# flowShield.net
KiCad netlist of a schematic drawn in EAGLE
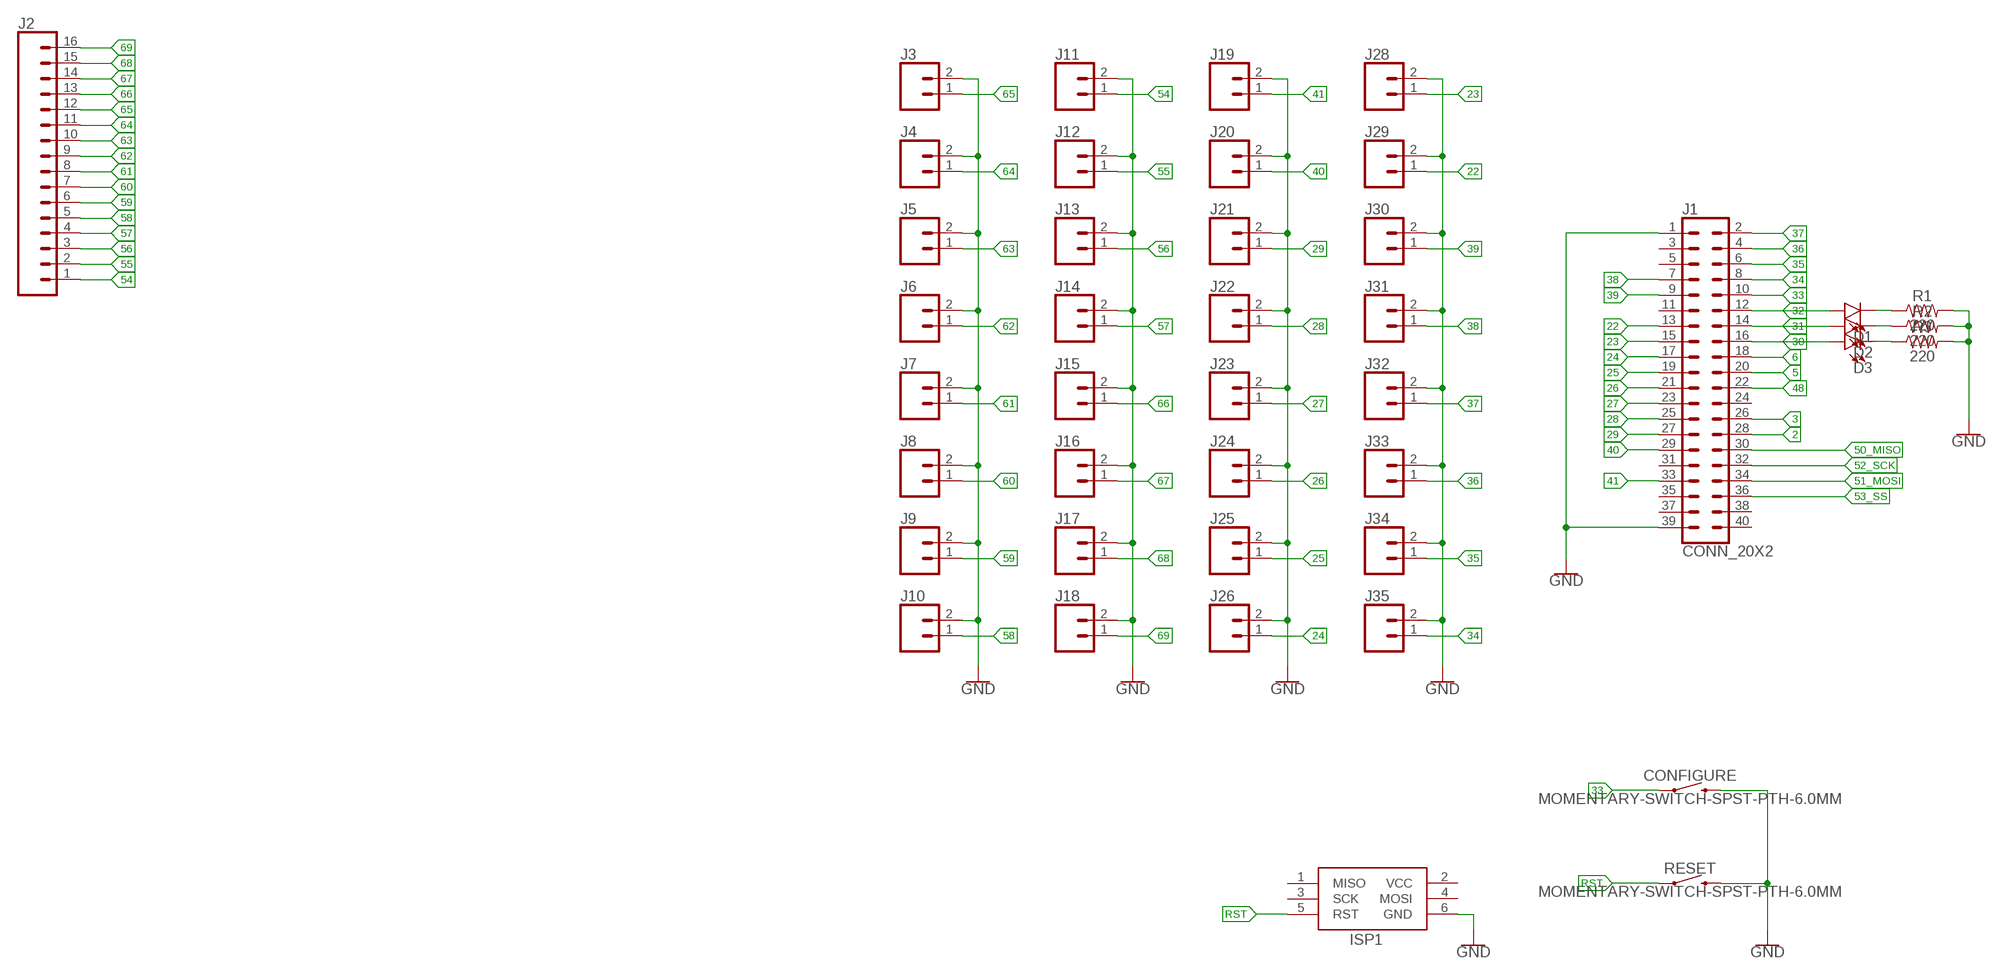
[diagram p0: schematic, sheet 1]

(export (version "E")
  (design (tool "Eeschema 10.0.6"))
  (components
    (comp (ref "CONFIGURE")
      (value "MOMENTARY-SWITCH-SPST-PTH-6.0MM")
      (footprint "eagle-import:TACTILE_SWITCH_PTH_6.0MM")
      (libsource (lib "eagle-import") (part "MOMENTARY-SWITCH-SPST-PTH-6.0MM"))
    )
    (comp (ref "D1")
      (value "LED3MM")
      (footprint "eagle-import:LED_3MM")
      (libsource (lib "eagle-import") (part "LED3MM"))
    )
    (comp (ref "D2")
      (value "LED3MM")
      (footprint "eagle-import:LED_3MM")
      (libsource (lib "eagle-import") (part "LED3MM"))
    )
    (comp (ref "D3")
      (value "LED3MM")
      (footprint "eagle-import:LED_3MM")
      (libsource (lib "eagle-import") (part "LED3MM"))
    )
    (comp (ref "ISP1")
      (value "ADAFRUIT_AVRISP-6")
      (footprint "eagle-import:ADAFRUIT_AVRISP")
      (libsource (lib "eagle-import") (part "ADAFRUIT_AVRISP-6"))
    )
    (comp (ref "J1")
      (value "CONN_20X2")
      (footprint "eagle-import:2X20")
      (libsource (lib "eagle-import") (part "CONN_20X2"))
    )
    (comp (ref "J2")
      (value "CONN_16")
      (footprint "eagle-import:1X16")
      (libsource (lib "eagle-import") (part "CONN_16"))
    )
    (comp (ref "J3")
      (value "CONN_025MM")
      (footprint "eagle-import:SCREWTERMINAL-5MM-2")
      (libsource (lib "eagle-import") (part "CONN_025MM"))
    )
    (comp (ref "J4")
      (value "CONN_025MM")
      (footprint "eagle-import:SCREWTERMINAL-5MM-2")
      (fields (field (name "SF_SKU") "PRT-08432"))
      (libsource (lib "eagle-import") (part "CONN_025MM"))
    )
    (comp (ref "J5")
      (value "CONN_025MM")
      (footprint "eagle-import:SCREWTERMINAL-5MM-2")
      (fields (field (name "SF_SKU") "PRT-08432"))
      (libsource (lib "eagle-import") (part "CONN_025MM"))
    )
    (comp (ref "J6")
      (value "CONN_025MM")
      (footprint "eagle-import:SCREWTERMINAL-5MM-2")
      (fields (field (name "SF_SKU") "PRT-08432"))
      (libsource (lib "eagle-import") (part "CONN_025MM"))
    )
    (comp (ref "J7")
      (value "CONN_025MM")
      (footprint "eagle-import:SCREWTERMINAL-5MM-2")
      (fields (field (name "SF_SKU") "PRT-08432"))
      (libsource (lib "eagle-import") (part "CONN_025MM"))
    )
    (comp (ref "J8")
      (value "CONN_025MM")
      (footprint "eagle-import:SCREWTERMINAL-5MM-2")
      (fields (field (name "SF_SKU") "PRT-08432"))
      (libsource (lib "eagle-import") (part "CONN_025MM"))
    )
    (comp (ref "J9")
      (value "CONN_025MM")
      (footprint "eagle-import:SCREWTERMINAL-5MM-2")
      (fields (field (name "SF_SKU") "PRT-08432"))
      (libsource (lib "eagle-import") (part "CONN_025MM"))
    )
    (comp (ref "J10")
      (value "CONN_025MM")
      (footprint "eagle-import:SCREWTERMINAL-5MM-2")
      (fields (field (name "SF_SKU") "PRT-08432"))
      (libsource (lib "eagle-import") (part "CONN_025MM"))
    )
    (comp (ref "J11")
      (value "CONN_025MM")
      (footprint "eagle-import:SCREWTERMINAL-5MM-2")
      (libsource (lib "eagle-import") (part "CONN_025MM"))
    )
    (comp (ref "J12")
      (value "CONN_025MM")
      (footprint "eagle-import:SCREWTERMINAL-5MM-2")
      (fields (field (name "SF_SKU") "PRT-08432"))
      (libsource (lib "eagle-import") (part "CONN_025MM"))
    )
    (comp (ref "J13")
      (value "CONN_025MM")
      (footprint "eagle-import:SCREWTERMINAL-5MM-2")
      (fields (field (name "SF_SKU") "PRT-08432"))
      (libsource (lib "eagle-import") (part "CONN_025MM"))
    )
    (comp (ref "J14")
      (value "CONN_025MM")
      (footprint "eagle-import:SCREWTERMINAL-5MM-2")
      (fields (field (name "SF_SKU") "PRT-08432"))
      (libsource (lib "eagle-import") (part "CONN_025MM"))
    )
    (comp (ref "J15")
      (value "CONN_025MM")
      (footprint "eagle-import:SCREWTERMINAL-5MM-2")
      (fields (field (name "SF_SKU") "PRT-08432"))
      (libsource (lib "eagle-import") (part "CONN_025MM"))
    )
    (comp (ref "J16")
      (value "CONN_025MM")
      (footprint "eagle-import:SCREWTERMINAL-5MM-2")
      (fields (field (name "SF_SKU") "PRT-08432"))
      (libsource (lib "eagle-import") (part "CONN_025MM"))
    )
    (comp (ref "J17")
      (value "CONN_025MM")
      (footprint "eagle-import:SCREWTERMINAL-5MM-2")
      (fields (field (name "SF_SKU") "PRT-08432"))
      (libsource (lib "eagle-import") (part "CONN_025MM"))
    )
    (comp (ref "J18")
      (value "CONN_025MM")
      (footprint "eagle-import:SCREWTERMINAL-5MM-2")
      (fields (field (name "SF_SKU") "PRT-08432"))
      (libsource (lib "eagle-import") (part "CONN_025MM"))
    )
    (comp (ref "J19")
      (value "CONN_025MM")
      (footprint "eagle-import:SCREWTERMINAL-5MM-2")
      (libsource (lib "eagle-import") (part "CONN_025MM"))
    )
    (comp (ref "J20")
      (value "CONN_025MM")
      (footprint "eagle-import:SCREWTERMINAL-5MM-2")
      (fields (field (name "SF_SKU") "PRT-08432"))
      (libsource (lib "eagle-import") (part "CONN_025MM"))
    )
    (comp (ref "J21")
      (value "CONN_025MM")
      (footprint "eagle-import:SCREWTERMINAL-5MM-2")
      (fields (field (name "SF_SKU") "PRT-08432"))
      (libsource (lib "eagle-import") (part "CONN_025MM"))
    )
    (comp (ref "J22")
      (value "CONN_025MM")
      (footprint "eagle-import:SCREWTERMINAL-5MM-2")
      (fields (field (name "SF_SKU") "PRT-08432"))
      (libsource (lib "eagle-import") (part "CONN_025MM"))
    )
    (comp (ref "J23")
      (value "CONN_025MM")
      (footprint "eagle-import:SCREWTERMINAL-5MM-2")
      (fields (field (name "SF_SKU") "PRT-08432"))
      (libsource (lib "eagle-import") (part "CONN_025MM"))
    )
    (comp (ref "J24")
      (value "CONN_025MM")
      (footprint "eagle-import:SCREWTERMINAL-5MM-2")
      (fields (field (name "SF_SKU") "PRT-08432"))
      (libsource (lib "eagle-import") (part "CONN_025MM"))
    )
    (comp (ref "J25")
      (value "CONN_025MM")
      (footprint "eagle-import:SCREWTERMINAL-5MM-2")
      (fields (field (name "SF_SKU") "PRT-08432"))
      (libsource (lib "eagle-import") (part "CONN_025MM"))
    )
    (comp (ref "J26")
      (value "CONN_025MM")
      (footprint "eagle-import:SCREWTERMINAL-5MM-2")
      (fields (field (name "SF_SKU") "PRT-08432"))
      (libsource (lib "eagle-import") (part "CONN_025MM"))
    )
    (comp (ref "J28")
      (value "CONN_025MM")
      (footprint "eagle-import:SCREWTERMINAL-5MM-2")
      (libsource (lib "eagle-import") (part "CONN_025MM"))
    )
    (comp (ref "J29")
      (value "CONN_025MM")
      (footprint "eagle-import:SCREWTERMINAL-5MM-2")
      (fields (field (name "SF_SKU") "PRT-08432"))
      (libsource (lib "eagle-import") (part "CONN_025MM"))
    )
    (comp (ref "J30")
      (value "CONN_025MM")
      (footprint "eagle-import:SCREWTERMINAL-5MM-2")
      (fields (field (name "SF_SKU") "PRT-08432"))
      (libsource (lib "eagle-import") (part "CONN_025MM"))
    )
    (comp (ref "J31")
      (value "CONN_025MM")
      (footprint "eagle-import:SCREWTERMINAL-5MM-2")
      (fields (field (name "SF_SKU") "PRT-08432"))
      (libsource (lib "eagle-import") (part "CONN_025MM"))
    )
    (comp (ref "J32")
      (value "CONN_025MM")
      (footprint "eagle-import:SCREWTERMINAL-5MM-2")
      (fields (field (name "SF_SKU") "PRT-08432"))
      (libsource (lib "eagle-import") (part "CONN_025MM"))
    )
    (comp (ref "J33")
      (value "CONN_025MM")
      (footprint "eagle-import:SCREWTERMINAL-5MM-2")
      (fields (field (name "SF_SKU") "PRT-08432"))
      (libsource (lib "eagle-import") (part "CONN_025MM"))
    )
    (comp (ref "J34")
      (value "CONN_025MM")
      (footprint "eagle-import:SCREWTERMINAL-5MM-2")
      (fields (field (name "SF_SKU") "PRT-08432"))
      (libsource (lib "eagle-import") (part "CONN_025MM"))
    )
    (comp (ref "J35")
      (value "CONN_025MM")
      (footprint "eagle-import:SCREWTERMINAL-5MM-2")
      (fields (field (name "SF_SKU") "PRT-08432"))
      (libsource (lib "eagle-import") (part "CONN_025MM"))
    )
    (comp (ref "R1")
      (value "220")
      (footprint "eagle-import:AXIAL-0.3")
      (libsource (lib "eagle-import") (part "1KOHM-HORIZ-1/4W-1%"))
    )
    (comp (ref "R2")
      (value "220")
      (footprint "eagle-import:AXIAL-0.3")
      (fields (field (name "PROD_ID") "RES-12182"))
      (libsource (lib "eagle-import") (part "1KOHM-HORIZ-1/4W-1%"))
    )
    (comp (ref "R3")
      (value "220")
      (footprint "eagle-import:AXIAL-0.3")
      (fields (field (name "PROD_ID") "RES-12182"))
      (libsource (lib "eagle-import") (part "1KOHM-HORIZ-1/4W-1%"))
    )
    (comp (ref "RESET")
      (value "MOMENTARY-SWITCH-SPST-PTH-6.0MM")
      (footprint "eagle-import:TACTILE_SWITCH_PTH_6.0MM")
      (libsource (lib "eagle-import") (part "MOMENTARY-SWITCH-SPST-PTH-6.0MM"))
    )
  )
  (nets
    (net (code "1") (name "/VCC") (class "Default")
      (node (ref "ISP1") (pin "2") (pinfunction "VCC_2") (pintype "power_in"))
    )
    (net (code "2") (name "2") (class "Default")
      (node (ref "J1") (pin "28") (pinfunction "28_28") (pintype "passive"))
    )
    (net (code "3") (name "3") (class "Default")
      (node (ref "J1") (pin "26") (pinfunction "26_26") (pintype "passive"))
    )
    (net (code "4") (name "5") (class "Default")
      (node (ref "J1") (pin "20") (pinfunction "20_20") (pintype "passive"))
    )
    (net (code "5") (name "6") (class "Default")
      (node (ref "J1") (pin "18") (pinfunction "18_18") (pintype "passive"))
    )
    (net (code "6") (name "22") (class "Default")
      (node (ref "J1") (pin "13") (pinfunction "13_13") (pintype "passive"))
      (node (ref "J29") (pin "1") (pinfunction "1_1") (pintype "passive"))
    )
    (net (code "7") (name "23") (class "Default")
      (node (ref "J1") (pin "15") (pinfunction "15_15") (pintype "passive"))
      (node (ref "J28") (pin "1") (pinfunction "1_1") (pintype "passive"))
    )
    (net (code "8") (name "24") (class "Default")
      (node (ref "J1") (pin "17") (pinfunction "17_17") (pintype "passive"))
      (node (ref "J26") (pin "1") (pinfunction "1_1") (pintype "passive"))
    )
    (net (code "9") (name "25") (class "Default")
      (node (ref "J1") (pin "19") (pinfunction "19_19") (pintype "passive"))
      (node (ref "J25") (pin "1") (pinfunction "1_1") (pintype "passive"))
    )
    (net (code "10") (name "26") (class "Default")
      (node (ref "J1") (pin "21") (pinfunction "21_21") (pintype "passive"))
      (node (ref "J24") (pin "1") (pinfunction "1_1") (pintype "passive"))
    )
    (net (code "11") (name "27") (class "Default")
      (node (ref "J1") (pin "23") (pinfunction "23_23") (pintype "passive"))
      (node (ref "J23") (pin "1") (pinfunction "1_1") (pintype "passive"))
    )
    (net (code "12") (name "28") (class "Default")
      (node (ref "J1") (pin "25") (pinfunction "25_25") (pintype "passive"))
      (node (ref "J22") (pin "1") (pinfunction "1_1") (pintype "passive"))
    )
    (net (code "13") (name "29") (class "Default")
      (node (ref "J1") (pin "27") (pinfunction "27_27") (pintype "passive"))
      (node (ref "J21") (pin "1") (pinfunction "1_1") (pintype "passive"))
    )
    (net (code "14") (name "30") (class "Default")
      (node (ref "D3") (pin "A") (pinfunction "A_A") (pintype "passive"))
      (node (ref "J1") (pin "16") (pinfunction "16_16") (pintype "passive"))
    )
    (net (code "15") (name "31") (class "Default")
      (node (ref "D2") (pin "A") (pinfunction "A_A") (pintype "passive"))
      (node (ref "J1") (pin "14") (pinfunction "14_14") (pintype "passive"))
    )
    (net (code "16") (name "32") (class "Default")
      (node (ref "D1") (pin "A") (pinfunction "A_A") (pintype "passive"))
      (node (ref "J1") (pin "12") (pinfunction "12_12") (pintype "passive"))
    )
    (net (code "17") (name "33") (class "Default")
      (node (ref "CONFIGURE") (pin "1") (pinfunction "1_1") (pintype "passive"))
      (node (ref "J1") (pin "10") (pinfunction "10_10") (pintype "passive"))
    )
    (net (code "18") (name "34") (class "Default")
      (node (ref "J1") (pin "8") (pinfunction "8_8") (pintype "passive"))
      (node (ref "J35") (pin "1") (pinfunction "1_1") (pintype "passive"))
    )
    (net (code "19") (name "35") (class "Default")
      (node (ref "J1") (pin "6") (pinfunction "6_6") (pintype "passive"))
      (node (ref "J34") (pin "1") (pinfunction "1_1") (pintype "passive"))
    )
    (net (code "20") (name "36") (class "Default")
      (node (ref "J1") (pin "4") (pinfunction "4_4") (pintype "passive"))
      (node (ref "J33") (pin "1") (pinfunction "1_1") (pintype "passive"))
    )
    (net (code "21") (name "37") (class "Default")
      (node (ref "J1") (pin "2") (pinfunction "2_2") (pintype "passive"))
      (node (ref "J32") (pin "1") (pinfunction "1_1") (pintype "passive"))
    )
    (net (code "22") (name "38") (class "Default")
      (node (ref "J1") (pin "7") (pinfunction "7_7") (pintype "passive"))
      (node (ref "J31") (pin "1") (pinfunction "1_1") (pintype "passive"))
    )
    (net (code "23") (name "39") (class "Default")
      (node (ref "J1") (pin "9") (pinfunction "9_9") (pintype "passive"))
      (node (ref "J30") (pin "1") (pinfunction "1_1") (pintype "passive"))
    )
    (net (code "24") (name "40") (class "Default")
      (node (ref "J1") (pin "29") (pinfunction "29_29") (pintype "passive"))
      (node (ref "J20") (pin "1") (pinfunction "1_1") (pintype "passive"))
    )
    (net (code "25") (name "41") (class "Default")
      (node (ref "J1") (pin "33") (pinfunction "33_33") (pintype "passive"))
      (node (ref "J19") (pin "1") (pinfunction "1_1") (pintype "passive"))
    )
    (net (code "26") (name "48") (class "Default")
      (node (ref "J1") (pin "22") (pinfunction "22_22") (pintype "passive"))
    )
    (net (code "27") (name "50_MISO") (class "Default")
      (node (ref "J1") (pin "30") (pinfunction "30_30") (pintype "passive"))
    )
    (net (code "28") (name "51_MOSI") (class "Default")
      (node (ref "J1") (pin "34") (pinfunction "34_34") (pintype "passive"))
    )
    (net (code "29") (name "52_SCK") (class "Default")
      (node (ref "J1") (pin "32") (pinfunction "32_32") (pintype "passive"))
    )
    (net (code "30") (name "53_SS") (class "Default")
      (node (ref "J1") (pin "36") (pinfunction "36_36") (pintype "passive"))
    )
    (net (code "31") (name "54") (class "Default")
      (node (ref "J11") (pin "1") (pinfunction "1_1") (pintype "passive"))
      (node (ref "J2") (pin "1") (pinfunction "1_1") (pintype "passive"))
    )
    (net (code "32") (name "55") (class "Default")
      (node (ref "J12") (pin "1") (pinfunction "1_1") (pintype "passive"))
      (node (ref "J2") (pin "2") (pinfunction "2_2") (pintype "passive"))
    )
    (net (code "33") (name "56") (class "Default")
      (node (ref "J13") (pin "1") (pinfunction "1_1") (pintype "passive"))
      (node (ref "J2") (pin "3") (pinfunction "3_3") (pintype "passive"))
    )
    (net (code "34") (name "57") (class "Default")
      (node (ref "J14") (pin "1") (pinfunction "1_1") (pintype "passive"))
      (node (ref "J2") (pin "4") (pinfunction "4_4") (pintype "passive"))
    )
    (net (code "35") (name "58") (class "Default")
      (node (ref "J10") (pin "1") (pinfunction "1_1") (pintype "passive"))
      (node (ref "J2") (pin "5") (pinfunction "5_5") (pintype "passive"))
    )
    (net (code "36") (name "59") (class "Default")
      (node (ref "J2") (pin "6") (pinfunction "6_6") (pintype "passive"))
      (node (ref "J9") (pin "1") (pinfunction "1_1") (pintype "passive"))
    )
    (net (code "37") (name "60") (class "Default")
      (node (ref "J2") (pin "7") (pinfunction "7_7") (pintype "passive"))
      (node (ref "J8") (pin "1") (pinfunction "1_1") (pintype "passive"))
    )
    (net (code "38") (name "61") (class "Default")
      (node (ref "J2") (pin "8") (pinfunction "8_8") (pintype "passive"))
      (node (ref "J7") (pin "1") (pinfunction "1_1") (pintype "passive"))
    )
    (net (code "39") (name "62") (class "Default")
      (node (ref "J2") (pin "9") (pinfunction "9_9") (pintype "passive"))
      (node (ref "J6") (pin "1") (pinfunction "1_1") (pintype "passive"))
    )
    (net (code "40") (name "63") (class "Default")
      (node (ref "J2") (pin "10") (pinfunction "10_10") (pintype "passive"))
      (node (ref "J5") (pin "1") (pinfunction "1_1") (pintype "passive"))
    )
    (net (code "41") (name "64") (class "Default")
      (node (ref "J2") (pin "11") (pinfunction "11_11") (pintype "passive"))
      (node (ref "J4") (pin "1") (pinfunction "1_1") (pintype "passive"))
    )
    (net (code "42") (name "65") (class "Default")
      (node (ref "J2") (pin "12") (pinfunction "12_12") (pintype "passive"))
      (node (ref "J3") (pin "1") (pinfunction "1_1") (pintype "passive"))
    )
    (net (code "43") (name "66") (class "Default")
      (node (ref "J15") (pin "1") (pinfunction "1_1") (pintype "passive"))
      (node (ref "J2") (pin "13") (pinfunction "13_13") (pintype "passive"))
    )
    (net (code "44") (name "67") (class "Default")
      (node (ref "J16") (pin "1") (pinfunction "1_1") (pintype "passive"))
      (node (ref "J2") (pin "14") (pinfunction "14_14") (pintype "passive"))
    )
    (net (code "45") (name "68") (class "Default")
      (node (ref "J17") (pin "1") (pinfunction "1_1") (pintype "passive"))
      (node (ref "J2") (pin "15") (pinfunction "15_15") (pintype "passive"))
    )
    (net (code "46") (name "69") (class "Default")
      (node (ref "J18") (pin "1") (pinfunction "1_1") (pintype "passive"))
      (node (ref "J2") (pin "16") (pinfunction "16_16") (pintype "passive"))
    )
    (net (code "47") (name "GND") (class "Default")
      (node (ref "CONFIGURE") (pin "3") (pinfunction "2_3") (pintype "passive"))
      (node (ref "ISP1") (pin "6") (pinfunction "GND_6") (pintype "power_in"))
      (node (ref "J1") (pin "1") (pinfunction "1_1") (pintype "passive"))
      (node (ref "J1") (pin "39") (pinfunction "39_39") (pintype "passive"))
      (node (ref "J10") (pin "2") (pinfunction "2_2") (pintype "passive"))
      (node (ref "J11") (pin "2") (pinfunction "2_2") (pintype "passive"))
      (node (ref "J12") (pin "2") (pinfunction "2_2") (pintype "passive"))
      (node (ref "J13") (pin "2") (pinfunction "2_2") (pintype "passive"))
      (node (ref "J14") (pin "2") (pinfunction "2_2") (pintype "passive"))
      (node (ref "J15") (pin "2") (pinfunction "2_2") (pintype "passive"))
      (node (ref "J16") (pin "2") (pinfunction "2_2") (pintype "passive"))
      (node (ref "J17") (pin "2") (pinfunction "2_2") (pintype "passive"))
      (node (ref "J18") (pin "2") (pinfunction "2_2") (pintype "passive"))
      (node (ref "J19") (pin "2") (pinfunction "2_2") (pintype "passive"))
      (node (ref "J20") (pin "2") (pinfunction "2_2") (pintype "passive"))
      (node (ref "J21") (pin "2") (pinfunction "2_2") (pintype "passive"))
      (node (ref "J22") (pin "2") (pinfunction "2_2") (pintype "passive"))
      (node (ref "J23") (pin "2") (pinfunction "2_2") (pintype "passive"))
      (node (ref "J24") (pin "2") (pinfunction "2_2") (pintype "passive"))
      (node (ref "J25") (pin "2") (pinfunction "2_2") (pintype "passive"))
      (node (ref "J26") (pin "2") (pinfunction "2_2") (pintype "passive"))
      (node (ref "J28") (pin "2") (pinfunction "2_2") (pintype "passive"))
      (node (ref "J29") (pin "2") (pinfunction "2_2") (pintype "passive"))
      (node (ref "J3") (pin "2") (pinfunction "2_2") (pintype "passive"))
      (node (ref "J30") (pin "2") (pinfunction "2_2") (pintype "passive"))
      (node (ref "J31") (pin "2") (pinfunction "2_2") (pintype "passive"))
      (node (ref "J32") (pin "2") (pinfunction "2_2") (pintype "passive"))
      (node (ref "J33") (pin "2") (pinfunction "2_2") (pintype "passive"))
      (node (ref "J34") (pin "2") (pinfunction "2_2") (pintype "passive"))
      (node (ref "J35") (pin "2") (pinfunction "2_2") (pintype "passive"))
      (node (ref "J4") (pin "2") (pinfunction "2_2") (pintype "passive"))
      (node (ref "J5") (pin "2") (pinfunction "2_2") (pintype "passive"))
      (node (ref "J6") (pin "2") (pinfunction "2_2") (pintype "passive"))
      (node (ref "J7") (pin "2") (pinfunction "2_2") (pintype "passive"))
      (node (ref "J8") (pin "2") (pinfunction "2_2") (pintype "passive"))
      (node (ref "J9") (pin "2") (pinfunction "2_2") (pintype "passive"))
      (node (ref "R1") (pin "P$2") (pinfunction "2_P$2") (pintype "passive"))
      (node (ref "R2") (pin "P$2") (pinfunction "2_P$2") (pintype "passive"))
      (node (ref "R3") (pin "P$2") (pinfunction "2_P$2") (pintype "passive"))
      (node (ref "RESET") (pin "3") (pinfunction "2_3") (pintype "passive"))
    )
    (net (code "48") (name "Net-(D1-C)") (class "Default")
      (node (ref "D1") (pin "K") (pinfunction "C_K") (pintype "passive"))
      (node (ref "R1") (pin "P$1") (pinfunction "1_P$1") (pintype "passive"))
    )
    (net (code "49") (name "Net-(D2-C)") (class "Default")
      (node (ref "D2") (pin "K") (pinfunction "C_K") (pintype "passive"))
      (node (ref "R2") (pin "P$1") (pinfunction "1_P$1") (pintype "passive"))
    )
    (net (code "50") (name "Net-(D3-C)") (class "Default")
      (node (ref "D3") (pin "K") (pinfunction "C_K") (pintype "passive"))
      (node (ref "R3") (pin "P$1") (pinfunction "1_P$1") (pintype "passive"))
    )
    (net (code "51") (name "RST") (class "Default")
      (node (ref "ISP1") (pin "5") (pinfunction "RST_5") (pintype "output"))
      (node (ref "RESET") (pin "1") (pinfunction "1_1") (pintype "passive"))
    )
    (net (code "52") (name "unconnected-(ISP1-MISO-Pad1)") (class "Default")
      (node (ref "ISP1") (pin "1") (pinfunction "MISO_1") (pintype "input"))
    )
    (net (code "53") (name "unconnected-(ISP1-MOSI-Pad4)") (class "Default")
      (node (ref "ISP1") (pin "4") (pinfunction "MOSI_4") (pintype "output"))
    )
    (net (code "54") (name "unconnected-(ISP1-SCK-Pad3)") (class "Default")
      (node (ref "ISP1") (pin "3") (pinfunction "SCK_3") (pintype "output"))
    )
    (net (code "55") (name "unconnected-(J1-Pad3)") (class "Default")
      (node (ref "J1") (pin "3") (pinfunction "3_3") (pintype "passive"))
    )
    (net (code "56") (name "unconnected-(J1-Pad5)") (class "Default")
      (node (ref "J1") (pin "5") (pinfunction "5_5") (pintype "passive"))
    )
    (net (code "57") (name "unconnected-(J1-Pad11)") (class "Default")
      (node (ref "J1") (pin "11") (pinfunction "11_11") (pintype "passive"))
    )
    (net (code "58") (name "unconnected-(J1-Pad24)") (class "Default")
      (node (ref "J1") (pin "24") (pinfunction "24_24") (pintype "passive"))
    )
    (net (code "59") (name "unconnected-(J1-Pad31)") (class "Default")
      (node (ref "J1") (pin "31") (pinfunction "31_31") (pintype "passive"))
    )
    (net (code "60") (name "unconnected-(J1-Pad35)") (class "Default")
      (node (ref "J1") (pin "35") (pinfunction "35_35") (pintype "passive"))
    )
    (net (code "61") (name "unconnected-(J1-Pad37)") (class "Default")
      (node (ref "J1") (pin "37") (pinfunction "37_37") (pintype "passive"))
    )
    (net (code "62") (name "unconnected-(J1-Pad38)") (class "Default")
      (node (ref "J1") (pin "38") (pinfunction "38_38") (pintype "passive"))
    )
    (net (code "63") (name "unconnected-(J1-Pad40)") (class "Default")
      (node (ref "J1") (pin "40") (pinfunction "40_40") (pintype "passive"))
    )
  )
)
